# relay_and_rtc.net
KiCad netlist of a schematic drawn in Altium Designer
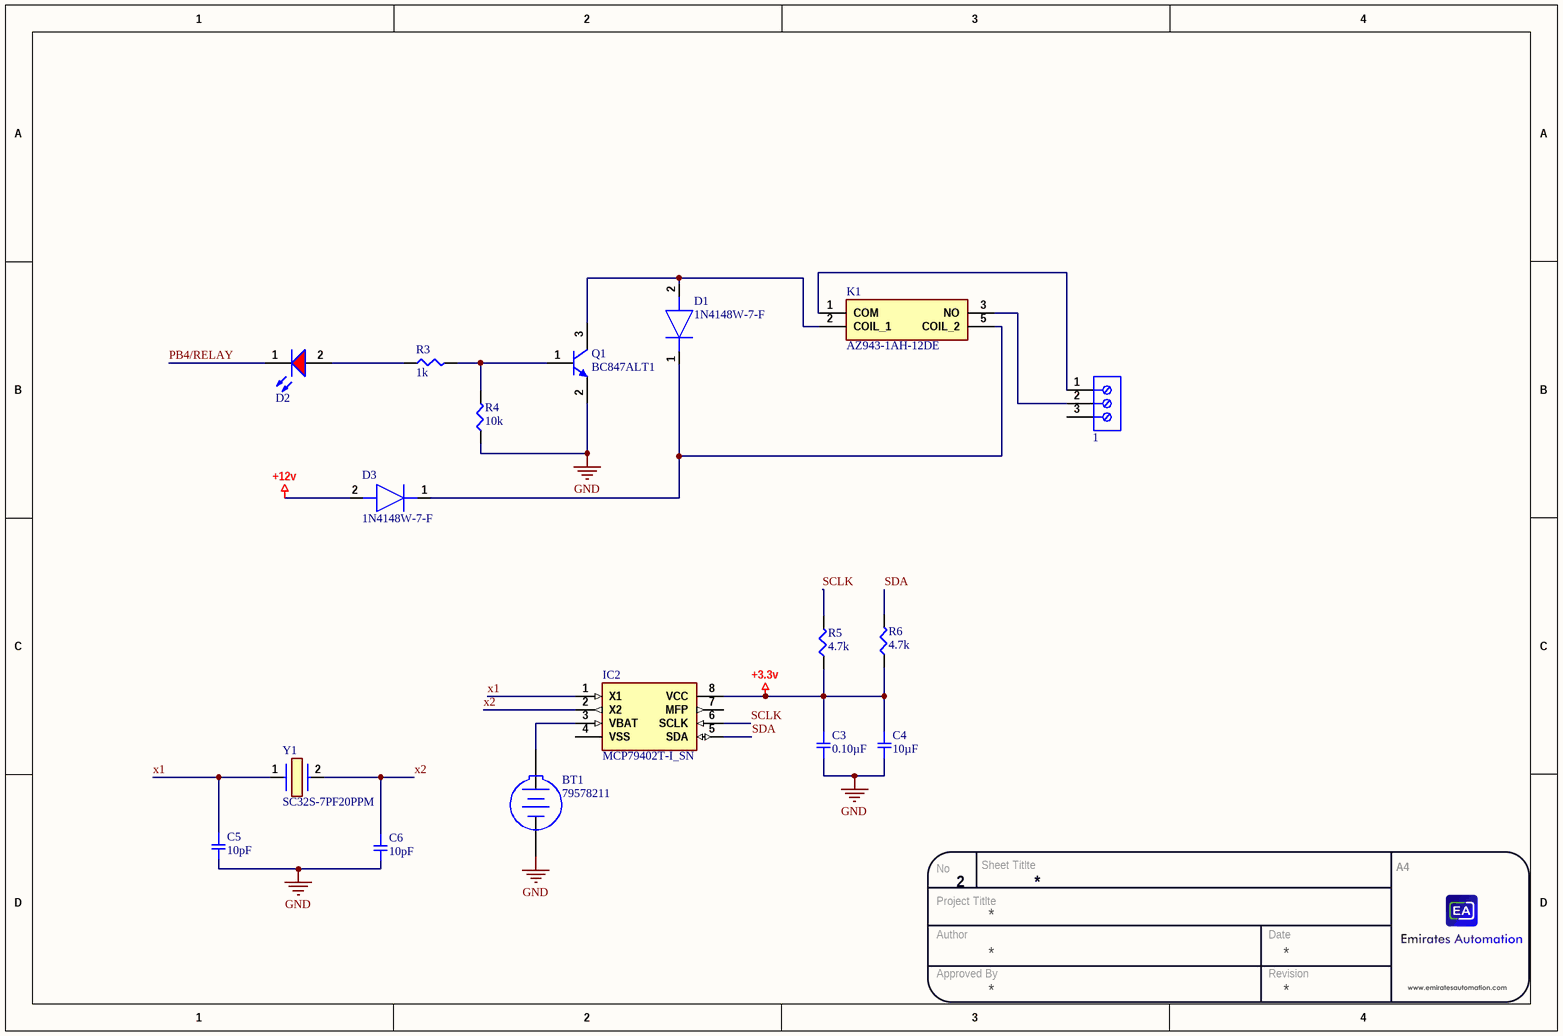
[diagram p0: relay and rtc.SchDoc]

(export (version "E")
  (design (tool "Eeschema 10.0.6"))
  (components
    (comp (ref "1")
      (value "691101710003")
      (footprint "691101710003")
      (description "WR-TBL Series 101 Horizontal Entry Modular, THT, pitch 5mm, 3p")
      (fields (field (name "MANUFACTURER") "Wurth Elektronik"))
      (libsource (lib "Terminal Blocks 2.54mm ") (part "691101710003"))
    )
    (comp (ref "BT1")
      (value "79578211")
      (footprint "79578211")
      (description "WA-BCPH Battery Holder, THT, Battery Type 2450")
      (fields (field (name "PUBLISHER") "Wurth Elektronik"))
      (libsource (lib "79528211_Altium_WA-BCPH_rev19a") (part "79578211"))
    )
    (comp (ref "C3")
      (value "0.10µF")
      (footprint "SMD-0603C")
      (description "CAP CER 0.1UF 16V X7R 0603")
      (fields
        (field (name "DIGI-KEY PART NUMBER") "490-5796-1-ND")
        (field (name "PART NUMBER") "GCJ188R71C104KA01D")
      )
      (libsource (lib "capacitor_murata_0603") (part "GCJ188R71C104KA01D"))
    )
    (comp (ref "C4")
      (value "10µF")
      (footprint "SMD-0603C")
      (description "CAP CER 10UF 6.3V X5R 0603")
      (fields
        (field (name "DIGI-KEY PART NUMBER") "490-10467-1-ND")
        (field (name "PART NUMBER") "GRM185R60J106ME15D")
      )
      (libsource (lib "capacitor_murata_0603") (part "GRM185R60J106ME15D"))
    )
    (comp (ref "C5")
      (value "10pF")
      (footprint "SMD-0603C")
      (description "CAP CER 10PF 50V NP0 0603")
      (fields
        (field (name "DIGI-KEY PART NUMBER") "490-12530-1-ND")
        (field (name "PART NUMBER") "GCM1885C1H100FA16D")
      )
      (libsource (lib "capacitor_murata_0603") (part "GCM1885C1H100FA16D"))
    )
    (comp (ref "C6")
      (value "10pF")
      (footprint "SMD-0603C")
      (description "CAP CER 10PF 50V NP0 0603")
      (fields
        (field (name "DIGI-KEY PART NUMBER") "490-12530-1-ND")
        (field (name "PART NUMBER") "GCM1885C1H100FA16D")
      )
      (libsource (lib "capacitor_murata_0603") (part "GCM1885C1H100FA16D"))
    )
    (comp (ref "D1")
      (value "1N4148W-7-F")
      (footprint "SamacSys:SOD3716X145N")
      (description "Diode")
      (fields (field (name "MOUSER PART NUMBER") "621-1N4148W-F"))
      (libsource (lib "SamacSys") (part "1N4148W-7-F"))
    )
    (comp (ref "D2")
      (value "Red, 2V, 140°")
      (footprint "WL-SMCD_0603")
      (description "WL-SMCD Mono-color Chip LED Diffused, SMT, size 0603, Red, 2V, 140°")
      (fields
        (field (name "MANUFACTURER PART NUMBER") "150060RS55040")
        (field (name "MANUFACTURER") "Wurth Elektronik")
      )
      (libsource (lib "wurth led 0603") (part "150060RS55040"))
    )
    (comp (ref "D3")
      (value "1N4148W-7-F")
      (footprint "SamacSys:SOD3716X145N")
      (description "Diode")
      (fields (field (name "MOUSER PART NUMBER") "621-1N4148W-F"))
      (libsource (lib "SamacSys") (part "1N4148W-7-F"))
    )
    (comp (ref "IC2")
      (value "MCP79402T-I_SN")
      (footprint "SamacSys:SOIC127P600X175-8N")
      (description "Integrated Circuit")
      (fields
        (field (name "MANUFACTURER_PART_NUMBER") "MCP79402T-I/SN")
        (field (name "MOUSER PART NUMBER") "579-MCP79402TISN")
      )
      (libsource (lib "SamacSys") (part "MCP79402T-I_SN"))
    )
    (comp (ref "K1")
      (value "AZ943-1AH-12DE")
      (footprint "SamacSys:AZ9431AH12DE")
      (description "Relay or Contactor")
      (libsource (lib "*") (part "AZ943-1AH-12DE"))
    )
    (comp (ref "Q1")
      (value "BC847ALT1")
      (footprint "ONSC-SOT-23-3-318-08_V")
      (description "General Purpose Transistor, NPN Silicon, 3-Pin SOT-23, Tape and Reel")
      (fields (field (name "MANUFACTURER") "On Semiconductor"))
      (libsource (lib "ON Semi General Purpose Transistors") (part "BC847ALT1"))
    )
    (comp (ref "R3")
      (value "1k")
      (footprint "SMD-0603-RES")
      (description "RES SMD 1K OHM 1% 1/10W 0603")
      (fields
        (field (name "PART NUMBER") "ERJ-3EKF1001V")
        (field (name "DIGI-KEY PART NUMBER") "P1.00KHCT-ND")
      )
      (libsource (lib "Panasonic_ERJ_0603") (part "ERJ-3EKF1001V"))
    )
    (comp (ref "R4")
      (value "10k")
      (footprint "SMD-0603-RES")
      (description "RES SMD 10K OHM 1% 1/10W 0603")
      (fields
        (field (name "PART NUMBER") "ERJ-3EKF1002V")
        (field (name "DIGI-KEY PART NUMBER") "P10.0KHCT-ND")
      )
      (libsource (lib "Panasonic_ERJ_0603") (part "ERJ-3EKF1002V"))
    )
    (comp (ref "R5")
      (value "4.7k")
      (footprint "SMD-0603-RES")
      (description "RES SMD 4.7K OHM 1% 1/10W 0603")
      (fields
        (field (name "PART NUMBER") "ERJ-3EKF4701V")
        (field (name "DIGI-KEY PART NUMBER") "P4.70KHCT-ND")
      )
      (libsource (lib "Panasonic_ERJ_0603") (part "ERJ-3EKF4701V"))
    )
    (comp (ref "R6")
      (value "4.7k")
      (footprint "SMD-0603-RES")
      (description "RES SMD 4.7K OHM 5% 1/10W 0603")
      (fields
        (field (name "PART NUMBER") "ERJ-3GEYJ472V")
        (field (name "DIGI-KEY PART NUMBER") "P4.7KGCT-ND")
      )
      (libsource (lib "Panasonic_ERJ_0603") (part "ERJ-3GEYJ472V"))
    )
    (comp (ref "Y1")
      (value "SC32S-7PF20PPM")
      (footprint "SamacSys:SC32S7PF20PPM")
      (description "Crystal or Oscillator")
      (fields (field (name "MOUSER PART NUMBER") "628-SC32S-7PF20PPM"))
      (libsource (lib "*") (part "SC32S-7PF20PPM"))
    )
  )
  (nets
    (net (code "1") (name "+3.3v") (class "Default")
      (node (ref "C3") (pin "1") (pinfunction "1_1") (pintype "passive"))
      (node (ref "C4") (pin "1") (pinfunction "1_1") (pintype "passive"))
      (node (ref "IC2") (pin "8") (pinfunction "VCC_8") (pintype "power_in"))
      (node (ref "R5") (pin "1") (pinfunction "1_1") (pintype "passive"))
      (node (ref "R6") (pin "1") (pinfunction "1_1") (pintype "passive"))
    )
    (net (code "2") (name "+12v") (class "Default")
      (node (ref "D3") (pin "2") (pinfunction "A_2") (pintype "passive"))
    )
    (net (code "3") (name "/PB4{slash}RELAY") (class "Default")
      (node (ref "D2") (pin "1") (pinfunction "K_1") (pintype "passive"))
    )
    (net (code "4") (name "/SCLK") (class "Default")
      (node (ref "IC2") (pin "6") (pinfunction "SCLK_6") (pintype "input"))
      (node (ref "R5") (pin "2") (pinfunction "2_2") (pintype "passive"))
    )
    (net (code "5") (name "/SDA") (class "Default")
      (node (ref "IC2") (pin "5") (pinfunction "SDA_5") (pintype "bidirectional"))
      (node (ref "R6") (pin "2") (pinfunction "2_2") (pintype "passive"))
    )
    (net (code "6") (name "/x1") (class "Default")
      (node (ref "C5") (pin "1") (pinfunction "1_1") (pintype "passive"))
      (node (ref "IC2") (pin "1") (pinfunction "X1_1") (pintype "input"))
      (node (ref "Y1") (pin "1") (pinfunction "1_1") (pintype "passive"))
    )
    (net (code "7") (name "/x2") (class "Default")
      (node (ref "C6") (pin "1") (pinfunction "1_1") (pintype "passive"))
      (node (ref "IC2") (pin "2") (pinfunction "X2_2") (pintype "output"))
      (node (ref "Y1") (pin "2") (pinfunction "2_2") (pintype "passive"))
    )
    (net (code "8") (name "GND") (class "Default")
      (node (ref "BT1") (pin "2") (pinfunction "-_2") (pintype "passive"))
      (node (ref "C3") (pin "2") (pinfunction "2_2") (pintype "passive"))
      (node (ref "C4") (pin "2") (pinfunction "2_2") (pintype "passive"))
      (node (ref "C5") (pin "2") (pinfunction "2_2") (pintype "passive"))
      (node (ref "C6") (pin "2") (pinfunction "2_2") (pintype "passive"))
      (node (ref "Q1") (pin "2") (pinfunction "E_2") (pintype "passive"))
      (node (ref "R4") (pin "1") (pinfunction "1_1") (pintype "passive"))
    )
    (net (code "9") (name "Net-(BT1-+)") (class "Default")
      (node (ref "BT1") (pin "1") (pinfunction "+_1") (pintype "passive"))
      (node (ref "IC2") (pin "3") (pinfunction "VBAT_3") (pintype "input"))
    )
    (net (code "10") (name "Net-(D1-A)") (class "Default")
      (node (ref "D1") (pin "2") (pinfunction "A_2") (pintype "passive"))
      (node (ref "K1") (pin "2") (pinfunction "COIL_1_2") (pintype "passive"))
      (node (ref "Q1") (pin "3") (pinfunction "C_3") (pintype "passive"))
    )
    (net (code "11") (name "Net-(D1-K)") (class "Default")
      (node (ref "D1") (pin "1") (pinfunction "K_1") (pintype "passive"))
      (node (ref "D3") (pin "1") (pinfunction "K_1") (pintype "passive"))
      (node (ref "K1") (pin "5") (pinfunction "COIL_2_5") (pintype "passive"))
    )
    (net (code "12") (name "Net-(D2-A)") (class "Default")
      (node (ref "D2") (pin "2") (pinfunction "A_2") (pintype "passive"))
      (node (ref "R3") (pin "1") (pinfunction "1_1") (pintype "passive"))
    )
    (net (code "13") (name "Net-(K1-COM)") (class "Default")
      (node (ref "1") (pin "1") (pinfunction "1_1") (pintype "passive"))
      (node (ref "K1") (pin "1") (pinfunction "COM_1") (pintype "passive"))
    )
    (net (code "14") (name "Net-(K1-NO)") (class "Default")
      (node (ref "1") (pin "2") (pinfunction "2_2") (pintype "passive"))
      (node (ref "K1") (pin "3") (pinfunction "NO_3") (pintype "passive"))
    )
    (net (code "15") (name "Net-(Q1-B)") (class "Default")
      (node (ref "Q1") (pin "1") (pinfunction "B_1") (pintype "passive"))
      (node (ref "R3") (pin "2") (pinfunction "2_2") (pintype "passive"))
      (node (ref "R4") (pin "2") (pinfunction "2_2") (pintype "passive"))
    )
    (net (code "16") (name "unconnected-(1-Pad3)") (class "Default")
      (node (ref "1") (pin "3") (pinfunction "3_3") (pintype "passive"))
    )
    (net (code "17") (name "unconnected-(IC2-MFP-Pad7)") (class "Default")
      (node (ref "IC2") (pin "7") (pinfunction "MFP_7") (pintype "output"))
    )
    (net (code "18") (name "unconnected-(IC2-VSS-Pad4)") (class "Default")
      (node (ref "IC2") (pin "4") (pinfunction "VSS_4") (pintype "power_in"))
    )
  )
)
